# stm32F103_64PIN_MINI_SYS.net
KiCad netlist of a schematic drawn in Altium Designer
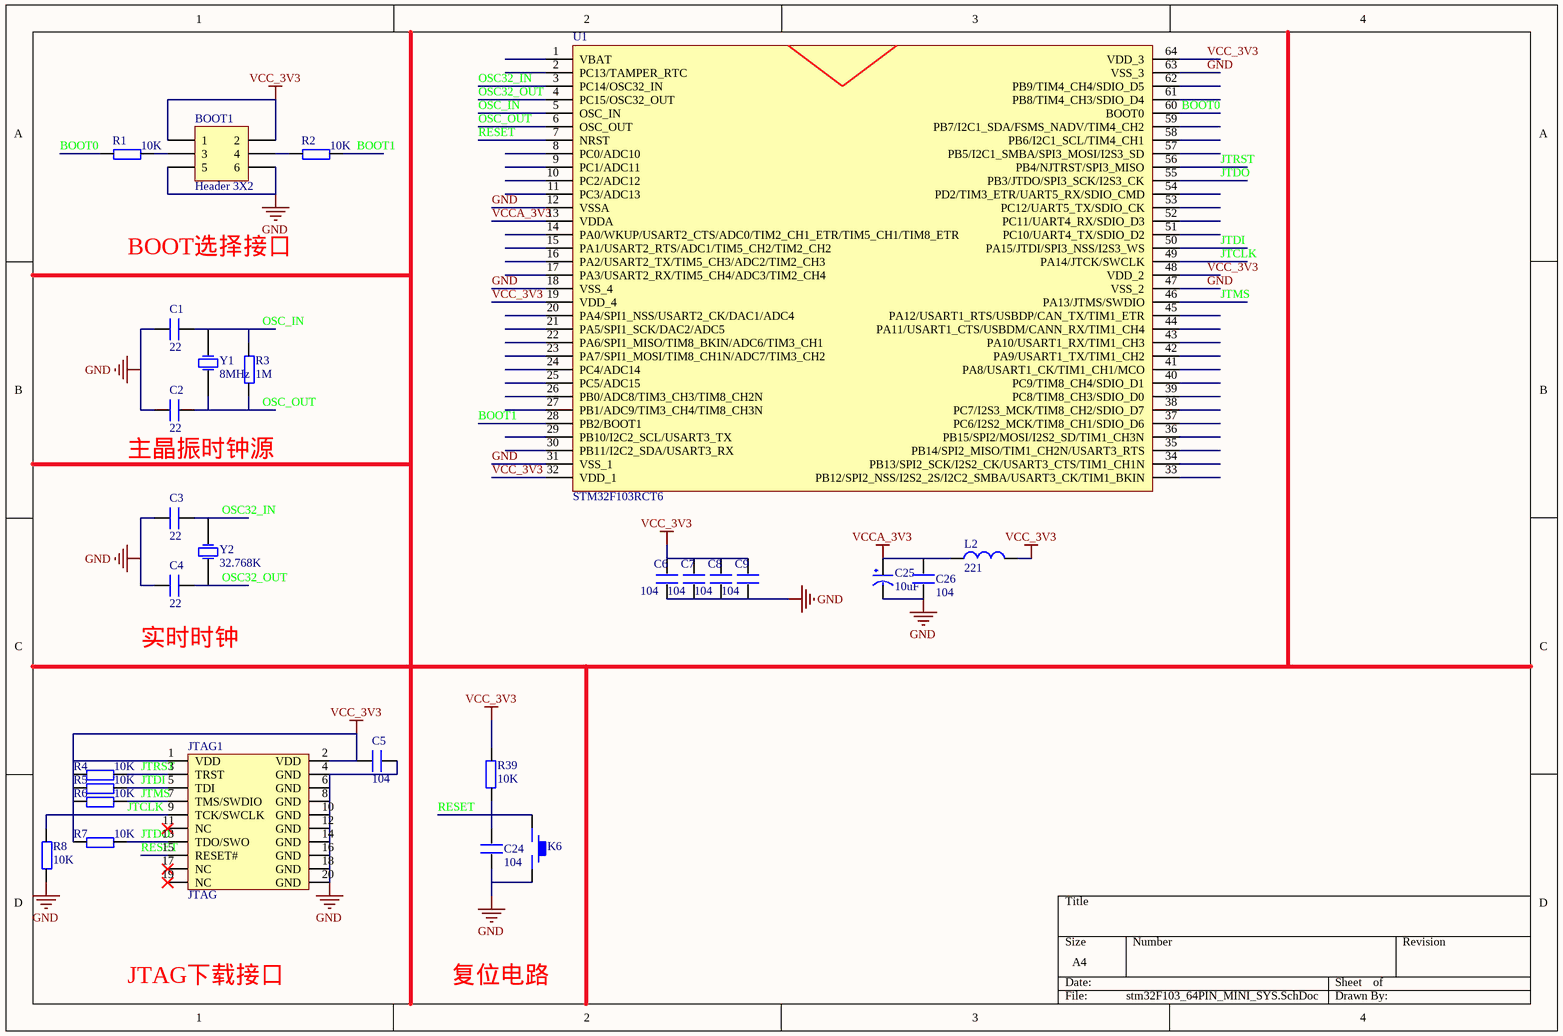
[diagram p0: stm32F103_64PIN_MINI_SYS.SchDoc]

(export (version "E")
  (design (tool "Eeschema 10.0.6"))
  (components
    (comp (ref "BOOT1")
      (value "Header 3X2")
      (footprint "HDR2X3")
      (description "Header, 3-Pin, Dual row")
      (fields (field (name "PUBLISHER") "Altium Limited"))
      (libsource (lib "MY_SCH_Lib") (part "Header 3X2"))
    )
    (comp (ref "C1") (value "22") (footprint "0603P") (libsource (lib "MY_SCH_Lib") (part "C")))
    (comp (ref "C2") (value "22") (footprint "0603P") (libsource (lib "MY_SCH_Lib") (part "C")))
    (comp (ref "C3") (value "22") (footprint "0603P") (libsource (lib "MY_SCH_Lib") (part "C")))
    (comp (ref "C4") (value "22") (footprint "0603P") (libsource (lib "MY_SCH_Lib") (part "C")))
    (comp (ref "C5") (value "104") (footprint "0603P") (libsource (lib "MY_SCH_Lib") (part "C")))
    (comp (ref "C6") (value "104") (footprint "0603P") (libsource (lib "MY_SCH_Lib") (part "C")))
    (comp (ref "C7") (value "104") (footprint "0603P") (libsource (lib "MY_SCH_Lib") (part "C")))
    (comp (ref "C8") (value "104") (footprint "0603P") (libsource (lib "MY_SCH_Lib") (part "C")))
    (comp (ref "C9") (value "104") (footprint "0603P") (libsource (lib "MY_SCH_Lib") (part "C")))
    (comp (ref "C24") (value "104") (footprint "0603P") (libsource (lib "MY_SCH_Lib") (part "C")))
    (comp (ref "C25") (value "10uF") (footprint "CC6.56.5") (libsource (lib "MY_SCH_Lib") (part "CAP")))
    (comp (ref "C26") (value "104") (footprint "0603P") (libsource (lib "MY_SCH_Lib") (part "C")))
    (comp (ref "JTAG1") (value "JTAG") (footprint "JTAG_20") (libsource (lib "MY_SCH_Lib") (part "JTAG")))
    (comp (ref "K6") (value "KEY") (footprint "KEY2") (libsource (lib "MY_SCH_Lib") (part "KEY")))
    (comp (ref "L2") (value "221") (footprint "INDC4532") (libsource (lib "MY_SCH_Lib") (part "Inductor")))
    (comp (ref "R1") (value "10K") (footprint "0603P") (libsource (lib "MY_SCH_Lib") (part "R")))
    (comp (ref "R2") (value "10K") (footprint "0603P") (libsource (lib "MY_SCH_Lib") (part "R")))
    (comp (ref "R3") (value "1M") (footprint "0603P") (libsource (lib "MY_SCH_Lib") (part "R")))
    (comp (ref "R4") (value "10K") (footprint "0603P") (libsource (lib "MY_SCH_Lib") (part "R")))
    (comp (ref "R5") (value "10K") (footprint "0603P") (libsource (lib "MY_SCH_Lib") (part "R")))
    (comp (ref "R6") (value "10K") (footprint "0603P") (libsource (lib "MY_SCH_Lib") (part "R")))
    (comp (ref "R7") (value "10K") (footprint "0603P") (libsource (lib "MY_SCH_Lib") (part "R")))
    (comp (ref "R8") (value "10K") (footprint "0603P") (libsource (lib "MY_SCH_Lib") (part "R")))
    (comp (ref "R39") (value "10K") (footprint "0603P") (libsource (lib "MY_SCH_Lib") (part "R")))
    (comp (ref "U1")
      (value "STM32F103RCT6")
      (footprint "STM-LQFP64_N")
      (libsource (lib "MY_SCH_Lib") (part "STM32F103RCT6"))
    )
    (comp (ref "Y1")
      (value "8MHz")
      (footprint "XTAL_US")
      (description "Crystal Oscillator")
      (fields (field (name "PUBLISHER") "Altium Limited"))
      (libsource (lib "MY_SCH_Lib") (part "XTAL"))
    )
    (comp (ref "Y2")
      (value "32.768K")
      (footprint "XTAL_US")
      (description "Crystal Oscillator")
      (fields (field (name "PUBLISHER") "Altium Limited"))
      (libsource (lib "MY_SCH_Lib") (part "XTAL"))
    )
  )
  (nets
    (net (code "1") (name "/BOOT0") (class "Default")
      (node (ref "R1") (pin "1") (pintype "passive"))
      (node (ref "U1") (pin "60") (pinfunction "BOOT0_60") (pintype "passive"))
    )
    (net (code "2") (name "/BOOT1") (class "Default")
      (node (ref "R2") (pin "2") (pintype "passive"))
      (node (ref "U1") (pin "28") (pinfunction "PB2/BOOT1_28") (pintype "passive"))
    )
    (net (code "3") (name "/JTCLK") (class "Default")
      (node (ref "JTAG1") (pin "9") (pinfunction "TCK/SWCLK_9") (pintype "passive"))
      (node (ref "R8") (pin "2") (pintype "passive"))
      (node (ref "U1") (pin "49") (pinfunction "PA14/JTCK/SWCLK_49") (pintype "passive"))
    )
    (net (code "4") (name "/JTDI") (class "Default")
      (node (ref "JTAG1") (pin "5") (pinfunction "TDI_5") (pintype "passive"))
      (node (ref "R5") (pin "2") (pintype "passive"))
      (node (ref "U1") (pin "50") (pinfunction "PA15/JTDI/SPI3_NSS/I2S3_WS_50") (pintype "passive"))
    )
    (net (code "5") (name "/JTDO") (class "Default")
      (node (ref "JTAG1") (pin "13") (pinfunction "TDO/SWO_13") (pintype "passive"))
      (node (ref "R7") (pin "2") (pintype "passive"))
      (node (ref "U1") (pin "55") (pinfunction "PB3/JTDO/SPI3_SCK/I2S3_CK_55") (pintype "passive"))
    )
    (net (code "6") (name "/JTMS") (class "Default")
      (node (ref "JTAG1") (pin "7") (pinfunction "TMS/SWDIO_7") (pintype "passive"))
      (node (ref "R6") (pin "2") (pintype "passive"))
      (node (ref "U1") (pin "46") (pinfunction "PA13/JTMS/SWDIO_46") (pintype "passive"))
    )
    (net (code "7") (name "/JTRST") (class "Default")
      (node (ref "JTAG1") (pin "3") (pinfunction "TRST_3") (pintype "passive"))
      (node (ref "R4") (pin "2") (pintype "passive"))
      (node (ref "U1") (pin "56") (pinfunction "PB4/NJTRST/SPI3_MISO_56") (pintype "passive"))
    )
    (net (code "8") (name "/OSC32_IN") (class "Default")
      (node (ref "C3") (pin "2") (pintype "passive"))
      (node (ref "U1") (pin "3") (pinfunction "PC14/OSC32_IN_3") (pintype "passive"))
      (node (ref "Y2") (pin "2") (pinfunction "OSC2_2") (pintype "passive"))
    )
    (net (code "9") (name "/OSC32_OUT") (class "Default")
      (node (ref "C4") (pin "2") (pintype "passive"))
      (node (ref "U1") (pin "4") (pinfunction "PC15/OSC32_OUT_4") (pintype "passive"))
      (node (ref "Y2") (pin "1") (pinfunction "OSC1_1") (pintype "passive"))
    )
    (net (code "10") (name "/OSC_IN") (class "Default")
      (node (ref "C1") (pin "2") (pintype "passive"))
      (node (ref "R3") (pin "2") (pintype "passive"))
      (node (ref "U1") (pin "5") (pinfunction "OSC_IN_5") (pintype "passive"))
      (node (ref "Y1") (pin "2") (pinfunction "OSC2_2") (pintype "passive"))
    )
    (net (code "11") (name "/OSC_OUT") (class "Default")
      (node (ref "C2") (pin "2") (pintype "passive"))
      (node (ref "R3") (pin "1") (pintype "passive"))
      (node (ref "U1") (pin "6") (pinfunction "OSC_OUT_6") (pintype "passive"))
      (node (ref "Y1") (pin "1") (pinfunction "OSC1_1") (pintype "passive"))
    )
    (net (code "12") (name "/RESET") (class "Default")
      (node (ref "C24") (pin "2") (pintype "passive"))
      (node (ref "JTAG1") (pin "15") (pinfunction "RESET#_15") (pintype "passive"))
      (node (ref "K6") (pin "2") (pinfunction "2_2") (pintype "passive"))
      (node (ref "R39") (pin "1") (pintype "passive"))
      (node (ref "U1") (pin "7") (pinfunction "NRST_7") (pintype "passive"))
    )
    (net (code "13") (name "GND") (class "Default")
      (node (ref "BOOT1") (pin "5") (pinfunction "5_5") (pintype "passive"))
      (node (ref "BOOT1") (pin "6") (pinfunction "6_6") (pintype "passive"))
      (node (ref "C1") (pin "1") (pintype "passive"))
      (node (ref "C2") (pin "1") (pintype "passive"))
      (node (ref "C24") (pin "1") (pintype "passive"))
      (node (ref "C25") (pin "2") (pinfunction "GND_2") (pintype "passive"))
      (node (ref "C26") (pin "1") (pintype "passive"))
      (node (ref "C3") (pin "1") (pintype "passive"))
      (node (ref "C4") (pin "1") (pintype "passive"))
      (node (ref "C5") (pin "2") (pintype "passive"))
      (node (ref "C6") (pin "1") (pintype "passive"))
      (node (ref "C7") (pin "1") (pintype "passive"))
      (node (ref "C8") (pin "1") (pintype "passive"))
      (node (ref "C9") (pin "1") (pintype "passive"))
      (node (ref "JTAG1") (pin "10") (pinfunction "GND_10") (pintype "passive"))
      (node (ref "JTAG1") (pin "12") (pinfunction "GND_12") (pintype "passive"))
      (node (ref "JTAG1") (pin "14") (pinfunction "GND_14") (pintype "passive"))
      (node (ref "JTAG1") (pin "16") (pinfunction "GND_16") (pintype "passive"))
      (node (ref "JTAG1") (pin "18") (pinfunction "GND_18") (pintype "passive"))
      (node (ref "JTAG1") (pin "20") (pinfunction "GND_20") (pintype "passive"))
      (node (ref "JTAG1") (pin "4") (pinfunction "GND_4") (pintype "passive"))
      (node (ref "JTAG1") (pin "6") (pinfunction "GND_6") (pintype "passive"))
      (node (ref "JTAG1") (pin "8") (pinfunction "GND_8") (pintype "passive"))
      (node (ref "K6") (pin "1") (pinfunction "1_1") (pintype "passive"))
      (node (ref "R8") (pin "1") (pintype "passive"))
      (node (ref "U1") (pin "12") (pinfunction "VSSA_12") (pintype "passive"))
      (node (ref "U1") (pin "18") (pinfunction "VSS_4_18") (pintype "passive"))
      (node (ref "U1") (pin "31") (pinfunction "VSS_1_31") (pintype "passive"))
      (node (ref "U1") (pin "47") (pinfunction "VSS_2_47") (pintype "passive"))
      (node (ref "U1") (pin "63") (pinfunction "VSS_3_63") (pintype "passive"))
    )
    (net (code "14") (name "Net-(BOOT1-Pad3)") (class "Default")
      (node (ref "BOOT1") (pin "3") (pinfunction "3_3") (pintype "passive"))
      (node (ref "R1") (pin "2") (pintype "passive"))
    )
    (net (code "15") (name "Net-(BOOT1-Pad4)") (class "Default")
      (node (ref "BOOT1") (pin "4") (pinfunction "4_4") (pintype "passive"))
      (node (ref "R2") (pin "1") (pintype "passive"))
    )
    (net (code "16") (name "VCCA_3V3") (class "Default")
      (node (ref "C25") (pin "1") (pinfunction "VCC_1") (pintype "passive"))
      (node (ref "C26") (pin "2") (pintype "passive"))
      (node (ref "L2") (pin "1") (pinfunction "1_1") (pintype "passive"))
      (node (ref "U1") (pin "13") (pinfunction "VDDA_13") (pintype "passive"))
    )
    (net (code "17") (name "VCC_3V3") (class "Default")
      (node (ref "BOOT1") (pin "1") (pinfunction "1_1") (pintype "passive"))
      (node (ref "BOOT1") (pin "2") (pinfunction "2_2") (pintype "passive"))
      (node (ref "C5") (pin "1") (pintype "passive"))
      (node (ref "C6") (pin "2") (pintype "passive"))
      (node (ref "C7") (pin "2") (pintype "passive"))
      (node (ref "C8") (pin "2") (pintype "passive"))
      (node (ref "C9") (pin "2") (pintype "passive"))
      (node (ref "JTAG1") (pin "1") (pinfunction "VDD_1") (pintype "passive"))
      (node (ref "JTAG1") (pin "2") (pinfunction "VDD_2") (pintype "passive"))
      (node (ref "L2") (pin "2") (pinfunction "2_2") (pintype "passive"))
      (node (ref "R39") (pin "2") (pintype "passive"))
      (node (ref "R4") (pin "1") (pintype "passive"))
      (node (ref "R5") (pin "1") (pintype "passive"))
      (node (ref "R6") (pin "1") (pintype "passive"))
      (node (ref "R7") (pin "1") (pintype "passive"))
      (node (ref "U1") (pin "19") (pinfunction "VDD_4_19") (pintype "passive"))
      (node (ref "U1") (pin "32") (pinfunction "VDD_1_32") (pintype "passive"))
      (node (ref "U1") (pin "48") (pinfunction "VDD_2_48") (pintype "passive"))
      (node (ref "U1") (pin "64") (pinfunction "VDD_3_64") (pintype "passive"))
    )
    (net (code "18") (name "unconnected-(JTAG1-NC-Pad11)") (class "Default")
      (node (ref "JTAG1") (pin "11") (pinfunction "NC_11") (pintype "passive+no_connect"))
    )
    (net (code "19") (name "unconnected-(JTAG1-NC-Pad17)") (class "Default")
      (node (ref "JTAG1") (pin "17") (pinfunction "NC_17") (pintype "passive+no_connect"))
    )
    (net (code "20") (name "unconnected-(JTAG1-NC-Pad19)") (class "Default")
      (node (ref "JTAG1") (pin "19") (pinfunction "NC_19") (pintype "passive+no_connect"))
    )
    (net (code "21") (name "unconnected-(U1-PA0{slash}WKUP{slash}USART2_CTS{slash}ADC0{slash}TIM2_CH1_ETR{slash}TIM5_CH1{slash}TIM8_ETR-Pad14)") (class "Default")
      (node (ref "U1") (pin "14") (pinfunction "PA0/WKUP/USART2_CTS/ADC0/TIM2_CH1_ETR/TIM5_CH1/TIM8_ETR_14") (pintype "passive"))
    )
    (net (code "22") (name "unconnected-(U1-PA1{slash}USART2_RTS{slash}ADC1{slash}TIM5_CH2{slash}TIM2_CH2-Pad15)") (class "Default")
      (node (ref "U1") (pin "15") (pinfunction "PA1/USART2_RTS/ADC1/TIM5_CH2/TIM2_CH2_15") (pintype "passive"))
    )
    (net (code "23") (name "unconnected-(U1-PA2{slash}USART2_TX{slash}TIM5_CH3{slash}ADC2{slash}TIM2_CH3-Pad16)") (class "Default")
      (node (ref "U1") (pin "16") (pinfunction "PA2/USART2_TX/TIM5_CH3/ADC2/TIM2_CH3_16") (pintype "passive"))
    )
    (net (code "24") (name "unconnected-(U1-PA3{slash}USART2_RX{slash}TIM5_CH4{slash}ADC3{slash}TIM2_CH4-Pad17)") (class "Default")
      (node (ref "U1") (pin "17") (pinfunction "PA3/USART2_RX/TIM5_CH4/ADC3/TIM2_CH4_17") (pintype "passive"))
    )
    (net (code "25") (name "unconnected-(U1-PA4{slash}SPI1_NSS{slash}USART2_CK{slash}DAC1{slash}ADC4-Pad20)") (class "Default")
      (node (ref "U1") (pin "20") (pinfunction "PA4/SPI1_NSS/USART2_CK/DAC1/ADC4_20") (pintype "passive"))
    )
    (net (code "26") (name "unconnected-(U1-PA5{slash}SPI1_SCK{slash}DAC2{slash}ADC5-Pad21)") (class "Default")
      (node (ref "U1") (pin "21") (pinfunction "PA5/SPI1_SCK/DAC2/ADC5_21") (pintype "passive"))
    )
    (net (code "27") (name "unconnected-(U1-PA6{slash}SPI1_MISO{slash}TIM8_BKIN{slash}ADC6{slash}TIM3_CH1-Pad22)") (class "Default")
      (node (ref "U1") (pin "22") (pinfunction "PA6/SPI1_MISO/TIM8_BKIN/ADC6/TIM3_CH1_22") (pintype "passive"))
    )
    (net (code "28") (name "unconnected-(U1-PA7{slash}SPI1_MOSI{slash}TIM8_CH1N{slash}ADC7{slash}TIM3_CH2-Pad23)") (class "Default")
      (node (ref "U1") (pin "23") (pinfunction "PA7/SPI1_MOSI/TIM8_CH1N/ADC7/TIM3_CH2_23") (pintype "passive"))
    )
    (net (code "29") (name "unconnected-(U1-PA8{slash}USART1_CK{slash}TIM1_CH1{slash}MCO-Pad41)") (class "Default")
      (node (ref "U1") (pin "41") (pinfunction "PA8/USART1_CK/TIM1_CH1/MCO_41") (pintype "passive"))
    )
    (net (code "30") (name "unconnected-(U1-PA9{slash}USART1_TX{slash}TIM1_CH2-Pad42)") (class "Default")
      (node (ref "U1") (pin "42") (pinfunction "PA9/USART1_TX/TIM1_CH2_42") (pintype "passive"))
    )
    (net (code "31") (name "unconnected-(U1-PA10{slash}USART1_RX{slash}TIM1_CH3-Pad43)") (class "Default")
      (node (ref "U1") (pin "43") (pinfunction "PA10/USART1_RX/TIM1_CH3_43") (pintype "passive"))
    )
    (net (code "32") (name "unconnected-(U1-PA11{slash}USART1_CTS{slash}USBDM{slash}CANN_RX{slash}TIM1_CH4-Pad44)") (class "Default")
      (node (ref "U1") (pin "44") (pinfunction "PA11/USART1_CTS/USBDM/CANN_RX/TIM1_CH4_44") (pintype "passive"))
    )
    (net (code "33") (name "unconnected-(U1-PA12{slash}USART1_RTS{slash}USBDP{slash}CAN_TX{slash}TIM1_ETR-Pad45)") (class "Default")
      (node (ref "U1") (pin "45") (pinfunction "PA12/USART1_RTS/USBDP/CAN_TX/TIM1_ETR_45") (pintype "passive"))
    )
    (net (code "34") (name "unconnected-(U1-PB0{slash}ADC8{slash}TIM3_CH3{slash}TIM8_CH2N-Pad26)") (class "Default")
      (node (ref "U1") (pin "26") (pinfunction "PB0/ADC8/TIM3_CH3/TIM8_CH2N_26") (pintype "passive"))
    )
    (net (code "35") (name "unconnected-(U1-PB1{slash}ADC9{slash}TIM3_CH4{slash}TIM8_CH3N-Pad27)") (class "Default")
      (node (ref "U1") (pin "27") (pinfunction "PB1/ADC9/TIM3_CH4/TIM8_CH3N_27") (pintype "passive"))
    )
    (net (code "36") (name "unconnected-(U1-PB5{slash}I2C1_SMBA{slash}SPI3_MOSI{slash}I2S3_SD-Pad57)") (class "Default")
      (node (ref "U1") (pin "57") (pinfunction "PB5/I2C1_SMBA/SPI3_MOSI/I2S3_SD_57") (pintype "passive"))
    )
    (net (code "37") (name "unconnected-(U1-PB6{slash}I2C1_SCL{slash}TIM4_CH1-Pad58)") (class "Default")
      (node (ref "U1") (pin "58") (pinfunction "PB6/I2C1_SCL/TIM4_CH1_58") (pintype "passive"))
    )
    (net (code "38") (name "unconnected-(U1-PB7{slash}I2C1_SDA{slash}FSMS_NADV{slash}TIM4_CH2-Pad59)") (class "Default")
      (node (ref "U1") (pin "59") (pinfunction "PB7/I2C1_SDA/FSMS_NADV/TIM4_CH2_59") (pintype "passive"))
    )
    (net (code "39") (name "unconnected-(U1-PB8{slash}TIM4_CH3{slash}SDIO_D4-Pad61)") (class "Default")
      (node (ref "U1") (pin "61") (pinfunction "PB8/TIM4_CH3/SDIO_D4_61") (pintype "passive"))
    )
    (net (code "40") (name "unconnected-(U1-PB9{slash}TIM4_CH4{slash}SDIO_D5-Pad62)") (class "Default")
      (node (ref "U1") (pin "62") (pinfunction "PB9/TIM4_CH4/SDIO_D5_62") (pintype "passive"))
    )
    (net (code "41") (name "unconnected-(U1-PB10{slash}I2C2_SCL{slash}USART3_TX-Pad29)") (class "Default")
      (node (ref "U1") (pin "29") (pinfunction "PB10/I2C2_SCL/USART3_TX_29") (pintype "passive"))
    )
    (net (code "42") (name "unconnected-(U1-PB11{slash}I2C2_SDA{slash}USART3_RX-Pad30)") (class "Default")
      (node (ref "U1") (pin "30") (pinfunction "PB11/I2C2_SDA/USART3_RX_30") (pintype "passive"))
    )
    (net (code "43") (name "unconnected-(U1-PB12{slash}SPI2_NSS{slash}I2S2_2S{slash}I2C2_SMBA{slash}USART3_CK{slash}TIM1_BKIN-Pad33)") (class "Default")
      (node (ref "U1") (pin "33") (pinfunction "PB12/SPI2_NSS/I2S2_2S/I2C2_SMBA/USART3_CK/TIM1_BKIN_33") (pintype "passive"))
    )
    (net (code "44") (name "unconnected-(U1-PB13{slash}SPI2_SCK{slash}I2S2_CK{slash}USART3_CTS{slash}TIM1_CH1N-Pad34)") (class "Default")
      (node (ref "U1") (pin "34") (pinfunction "PB13/SPI2_SCK/I2S2_CK/USART3_CTS/TIM1_CH1N_34") (pintype "passive"))
    )
    (net (code "45") (name "unconnected-(U1-PB14{slash}SPI2_MISO{slash}TIM1_CH2N{slash}USART3_RTS-Pad35)") (class "Default")
      (node (ref "U1") (pin "35") (pinfunction "PB14/SPI2_MISO/TIM1_CH2N/USART3_RTS_35") (pintype "passive"))
    )
    (net (code "46") (name "unconnected-(U1-PB15{slash}SPI2{slash}MOSI{slash}I2S2_SD{slash}TIM1_CH3N-Pad36)") (class "Default")
      (node (ref "U1") (pin "36") (pinfunction "PB15/SPI2/MOSI/I2S2_SD/TIM1_CH3N_36") (pintype "passive"))
    )
    (net (code "47") (name "unconnected-(U1-PC0{slash}ADC10-Pad8)") (class "Default")
      (node (ref "U1") (pin "8") (pinfunction "PC0/ADC10_8") (pintype "passive"))
    )
    (net (code "48") (name "unconnected-(U1-PC1{slash}ADC11-Pad9)") (class "Default")
      (node (ref "U1") (pin "9") (pinfunction "PC1/ADC11_9") (pintype "passive"))
    )
    (net (code "49") (name "unconnected-(U1-PC2{slash}ADC12-Pad10)") (class "Default")
      (node (ref "U1") (pin "10") (pinfunction "PC2/ADC12_10") (pintype "passive"))
    )
    (net (code "50") (name "unconnected-(U1-PC3{slash}ADC13-Pad11)") (class "Default")
      (node (ref "U1") (pin "11") (pinfunction "PC3/ADC13_11") (pintype "passive"))
    )
    (net (code "51") (name "unconnected-(U1-PC4{slash}ADC14-Pad24)") (class "Default")
      (node (ref "U1") (pin "24") (pinfunction "PC4/ADC14_24") (pintype "passive"))
    )
    (net (code "52") (name "unconnected-(U1-PC5{slash}ADC15-Pad25)") (class "Default")
      (node (ref "U1") (pin "25") (pinfunction "PC5/ADC15_25") (pintype "passive"))
    )
    (net (code "53") (name "unconnected-(U1-PC6{slash}I2S2_MCK{slash}TIM8_CH1{slash}SDIO_D6-Pad37)") (class "Default")
      (node (ref "U1") (pin "37") (pinfunction "PC6/I2S2_MCK/TIM8_CH1/SDIO_D6_37") (pintype "passive"))
    )
    (net (code "54") (name "unconnected-(U1-PC7{slash}I2S3_MCK{slash}TIM8_CH2{slash}SDIO_D7-Pad38)") (class "Default")
      (node (ref "U1") (pin "38") (pinfunction "PC7/I2S3_MCK/TIM8_CH2/SDIO_D7_38") (pintype "passive"))
    )
    (net (code "55") (name "unconnected-(U1-PC8{slash}TIM8_CH3{slash}SDIO_D0-Pad39)") (class "Default")
      (node (ref "U1") (pin "39") (pinfunction "PC8/TIM8_CH3/SDIO_D0_39") (pintype "passive"))
    )
    (net (code "56") (name "unconnected-(U1-PC9{slash}TIM8_CH4{slash}SDIO_D1-Pad40)") (class "Default")
      (node (ref "U1") (pin "40") (pinfunction "PC9/TIM8_CH4/SDIO_D1_40") (pintype "passive"))
    )
    (net (code "57") (name "unconnected-(U1-PC10{slash}UART4_TX{slash}SDIO_D2-Pad51)") (class "Default")
      (node (ref "U1") (pin "51") (pinfunction "PC10/UART4_TX/SDIO_D2_51") (pintype "passive"))
    )
    (net (code "58") (name "unconnected-(U1-PC11{slash}UART4_RX{slash}SDIO_D3-Pad52)") (class "Default")
      (node (ref "U1") (pin "52") (pinfunction "PC11/UART4_RX/SDIO_D3_52") (pintype "passive"))
    )
    (net (code "59") (name "unconnected-(U1-PC12{slash}UART5_TX{slash}SDIO_CK-Pad53)") (class "Default")
      (node (ref "U1") (pin "53") (pinfunction "PC12/UART5_TX/SDIO_CK_53") (pintype "passive"))
    )
    (net (code "60") (name "unconnected-(U1-PC13{slash}TAMPER_RTC-Pad2)") (class "Default")
      (node (ref "U1") (pin "2") (pinfunction "PC13/TAMPER_RTC_2") (pintype "passive"))
    )
    (net (code "61") (name "unconnected-(U1-PD2{slash}TIM3_ETR{slash}UART5_RX{slash}SDIO_CMD-Pad54)") (class "Default")
      (node (ref "U1") (pin "54") (pinfunction "PD2/TIM3_ETR/UART5_RX/SDIO_CMD_54") (pintype "passive"))
    )
    (net (code "62") (name "unconnected-(U1-VBAT-Pad1)") (class "Default")
      (node (ref "U1") (pin "1") (pinfunction "VBAT_1") (pintype "passive"))
    )
  )
)
